# peripherals.net
KiCad netlist of a schematic drawn in Altium Designer
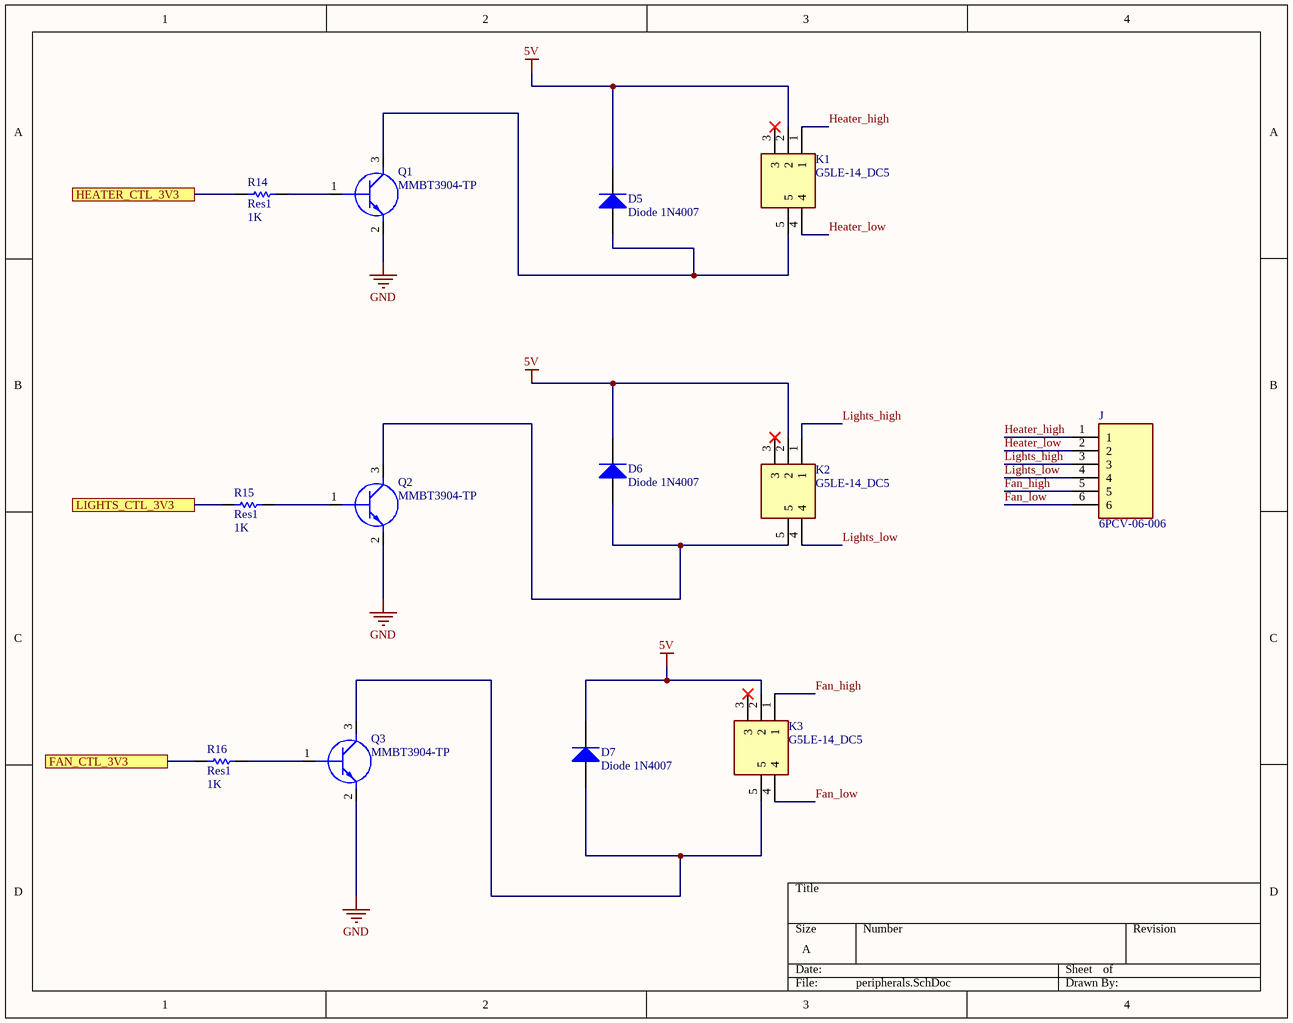
[diagram p0: peripherals.SchDoc]

(export (version "E")
  (design (tool "Eeschema 10.0.6"))
  (components
    (comp (ref "D5")
      (value "Diode 1N4007")
      (footprint "DO-41")
      (description "1 Amp General Purpose Rectifier")
      (fields (field (name "PUBLISHER") "Altium Limited"))
      (libsource (lib "Miscellaneous Devices") (part "Diode 1N4007"))
    )
    (comp (ref "D6")
      (value "Diode 1N4007")
      (footprint "DO-41")
      (description "1 Amp General Purpose Rectifier")
      (fields (field (name "PUBLISHER") "Altium Limited"))
      (libsource (lib "Miscellaneous Devices") (part "Diode 1N4007"))
    )
    (comp (ref "D7")
      (value "Diode 1N4007")
      (footprint "DO-41")
      (description "1 Amp General Purpose Rectifier")
      (fields (field (name "PUBLISHER") "Altium Limited"))
      (libsource (lib "Miscellaneous Devices") (part "Diode 1N4007"))
    )
    (comp (ref "J")
      (value "6PCV-06-006")
      (footprint "TE_9-1437652-5")
      (description "Buchanan 6 Position 9.53 mm Pitch Single Row 12-22 AWG Tri-Barrier Strip")
      (fields (field (name "MF") "TE Connectivity"))
      (libsource (lib "6PCV-06-006") (part "6PCV-06-006"))
    )
    (comp (ref "K1")
      (value "G5LE-14_DC5")
      (footprint "SamacSys:G5LE-1A")
      (description "Relay or Contactor")
      (fields (field (name "MANUFACTURER_PART_NUMBER") "G5LE-14 DC5"))
      (libsource (lib "*") (part "G5LE-14_DC5"))
    )
    (comp (ref "K2")
      (value "G5LE-14_DC5")
      (footprint "SamacSys:G5LE-1A")
      (description "Relay or Contactor")
      (fields (field (name "MANUFACTURER_PART_NUMBER") "G5LE-14 DC5"))
      (libsource (lib "*") (part "G5LE-14_DC5"))
    )
    (comp (ref "K3")
      (value "G5LE-14_DC5")
      (footprint "SamacSys:G5LE-1A")
      (description "Relay or Contactor")
      (fields (field (name "MANUFACTURER_PART_NUMBER") "G5LE-14 DC5"))
      (libsource (lib "*") (part "G5LE-14_DC5"))
    )
    (comp (ref "Q1")
      (value "MMBT3904-TP")
      (footprint "SamacSys:SI2305TP")
      (description "Transistor BJT NPN")
      (fields (field (name "MOUSER PART NUMBER") "833-MMBT3904-TP"))
      (libsource (lib "*") (part "MMBT3904-TP"))
    )
    (comp (ref "Q2")
      (value "MMBT3904-TP")
      (footprint "SamacSys:SI2305TP")
      (description "Transistor BJT NPN")
      (fields (field (name "MOUSER PART NUMBER") "833-MMBT3904-TP"))
      (libsource (lib "*") (part "MMBT3904-TP"))
    )
    (comp (ref "Q3")
      (value "MMBT3904-TP")
      (footprint "SamacSys:SI2305TP")
      (description "Transistor BJT NPN")
      (fields (field (name "MOUSER PART NUMBER") "833-MMBT3904-TP"))
      (libsource (lib "*") (part "MMBT3904-TP"))
    )
    (comp (ref "R14")
      (value "Res1")
      (footprint "AXIAL-0.3")
      (description "Resistor")
      (fields (field (name "ALTIUM_VALUE") "1K") (field (name "PUBLISHER") "Altium Limited"))
      (libsource (lib "Miscellaneous Devices") (part "Res1"))
    )
    (comp (ref "R15")
      (value "Res1")
      (footprint "AXIAL-0.3")
      (description "Resistor")
      (fields (field (name "ALTIUM_VALUE") "1K") (field (name "PUBLISHER") "Altium Limited"))
      (libsource (lib "Miscellaneous Devices") (part "Res1"))
    )
    (comp (ref "R16")
      (value "Res1")
      (footprint "AXIAL-0.3")
      (description "Resistor")
      (fields (field (name "ALTIUM_VALUE") "1K") (field (name "PUBLISHER") "Altium Limited"))
      (libsource (lib "Miscellaneous Devices") (part "Res1"))
    )
  )
  (nets
    (net (code "1") (name "/FAN_CTL_3V3") (class "Default")
      (node (ref "R16") (pin "1") (pinfunction "1_1") (pintype "passive"))
    )
    (net (code "2") (name "/Fan_high") (class "Default")
      (node (ref "J") (pin "5") (pinfunction "5_5") (pintype "passive"))
      (node (ref "K3") (pin "1") (pinfunction "1_1") (pintype "passive"))
    )
    (net (code "3") (name "/Fan_low") (class "Default")
      (node (ref "J") (pin "6") (pinfunction "6_6") (pintype "passive"))
      (node (ref "K3") (pin "4") (pinfunction "4_4") (pintype "passive"))
    )
    (net (code "4") (name "/HEATER_CTL_3V3") (class "Default")
      (node (ref "R14") (pin "1") (pinfunction "1_1") (pintype "passive"))
    )
    (net (code "5") (name "/Heater_high") (class "Default")
      (node (ref "J") (pin "1") (pinfunction "1_1") (pintype "passive"))
      (node (ref "K1") (pin "1") (pinfunction "1_1") (pintype "passive"))
    )
    (net (code "6") (name "/Heater_low") (class "Default")
      (node (ref "J") (pin "2") (pinfunction "2_2") (pintype "passive"))
      (node (ref "K1") (pin "4") (pinfunction "4_4") (pintype "passive"))
    )
    (net (code "7") (name "/LIGHTS_CTL_3V3") (class "Default")
      (node (ref "R15") (pin "1") (pinfunction "1_1") (pintype "passive"))
    )
    (net (code "8") (name "/Lights_high") (class "Default")
      (node (ref "J") (pin "3") (pinfunction "3_3") (pintype "passive"))
      (node (ref "K2") (pin "1") (pinfunction "1_1") (pintype "passive"))
    )
    (net (code "9") (name "/Lights_low") (class "Default")
      (node (ref "J") (pin "4") (pinfunction "4_4") (pintype "passive"))
      (node (ref "K2") (pin "4") (pinfunction "4_4") (pintype "passive"))
    )
    (net (code "10") (name "5V") (class "Default")
      (node (ref "D5") (pin "2") (pinfunction "K_2") (pintype "passive"))
      (node (ref "D6") (pin "2") (pinfunction "K_2") (pintype "passive"))
      (node (ref "D7") (pin "2") (pinfunction "K_2") (pintype "passive"))
      (node (ref "K1") (pin "2") (pinfunction "2_2") (pintype "passive"))
      (node (ref "K2") (pin "2") (pinfunction "2_2") (pintype "passive"))
      (node (ref "K3") (pin "2") (pinfunction "2_2") (pintype "passive"))
    )
    (net (code "11") (name "GND") (class "Default")
      (node (ref "Q1") (pin "2") (pinfunction "E_2") (pintype "passive"))
      (node (ref "Q2") (pin "2") (pinfunction "E_2") (pintype "passive"))
      (node (ref "Q3") (pin "2") (pinfunction "E_2") (pintype "passive"))
    )
    (net (code "12") (name "Net-(D5-A)") (class "Default")
      (node (ref "D5") (pin "1") (pinfunction "A_1") (pintype "passive"))
      (node (ref "K1") (pin "5") (pinfunction "5_5") (pintype "passive"))
      (node (ref "Q1") (pin "3") (pinfunction "C_3") (pintype "passive"))
    )
    (net (code "13") (name "Net-(D6-A)") (class "Default")
      (node (ref "D6") (pin "1") (pinfunction "A_1") (pintype "passive"))
      (node (ref "K2") (pin "5") (pinfunction "5_5") (pintype "passive"))
      (node (ref "Q2") (pin "3") (pinfunction "C_3") (pintype "passive"))
    )
    (net (code "14") (name "Net-(D7-A)") (class "Default")
      (node (ref "D7") (pin "1") (pinfunction "A_1") (pintype "passive"))
      (node (ref "K3") (pin "5") (pinfunction "5_5") (pintype "passive"))
      (node (ref "Q3") (pin "3") (pinfunction "C_3") (pintype "passive"))
    )
    (net (code "15") (name "Net-(Q1-B)") (class "Default")
      (node (ref "Q1") (pin "1") (pinfunction "B_1") (pintype "passive"))
      (node (ref "R14") (pin "2") (pinfunction "2_2") (pintype "passive"))
    )
    (net (code "16") (name "Net-(Q2-B)") (class "Default")
      (node (ref "Q2") (pin "1") (pinfunction "B_1") (pintype "passive"))
      (node (ref "R15") (pin "2") (pinfunction "2_2") (pintype "passive"))
    )
    (net (code "17") (name "Net-(Q3-B)") (class "Default")
      (node (ref "Q3") (pin "1") (pinfunction "B_1") (pintype "passive"))
      (node (ref "R16") (pin "2") (pinfunction "2_2") (pintype "passive"))
    )
    (net (code "18") (name "unconnected-(K1-Pad3)") (class "Default")
      (node (ref "K1") (pin "3") (pinfunction "3_3") (pintype "passive+no_connect"))
    )
    (net (code "19") (name "unconnected-(K2-Pad3)") (class "Default")
      (node (ref "K2") (pin "3") (pinfunction "3_3") (pintype "passive+no_connect"))
    )
    (net (code "20") (name "unconnected-(K3-Pad3)") (class "Default")
      (node (ref "K3") (pin "3") (pinfunction "3_3") (pintype "passive+no_connect"))
    )
  )
)
